# Power.net
KiCad netlist of a schematic drawn in EAGLE
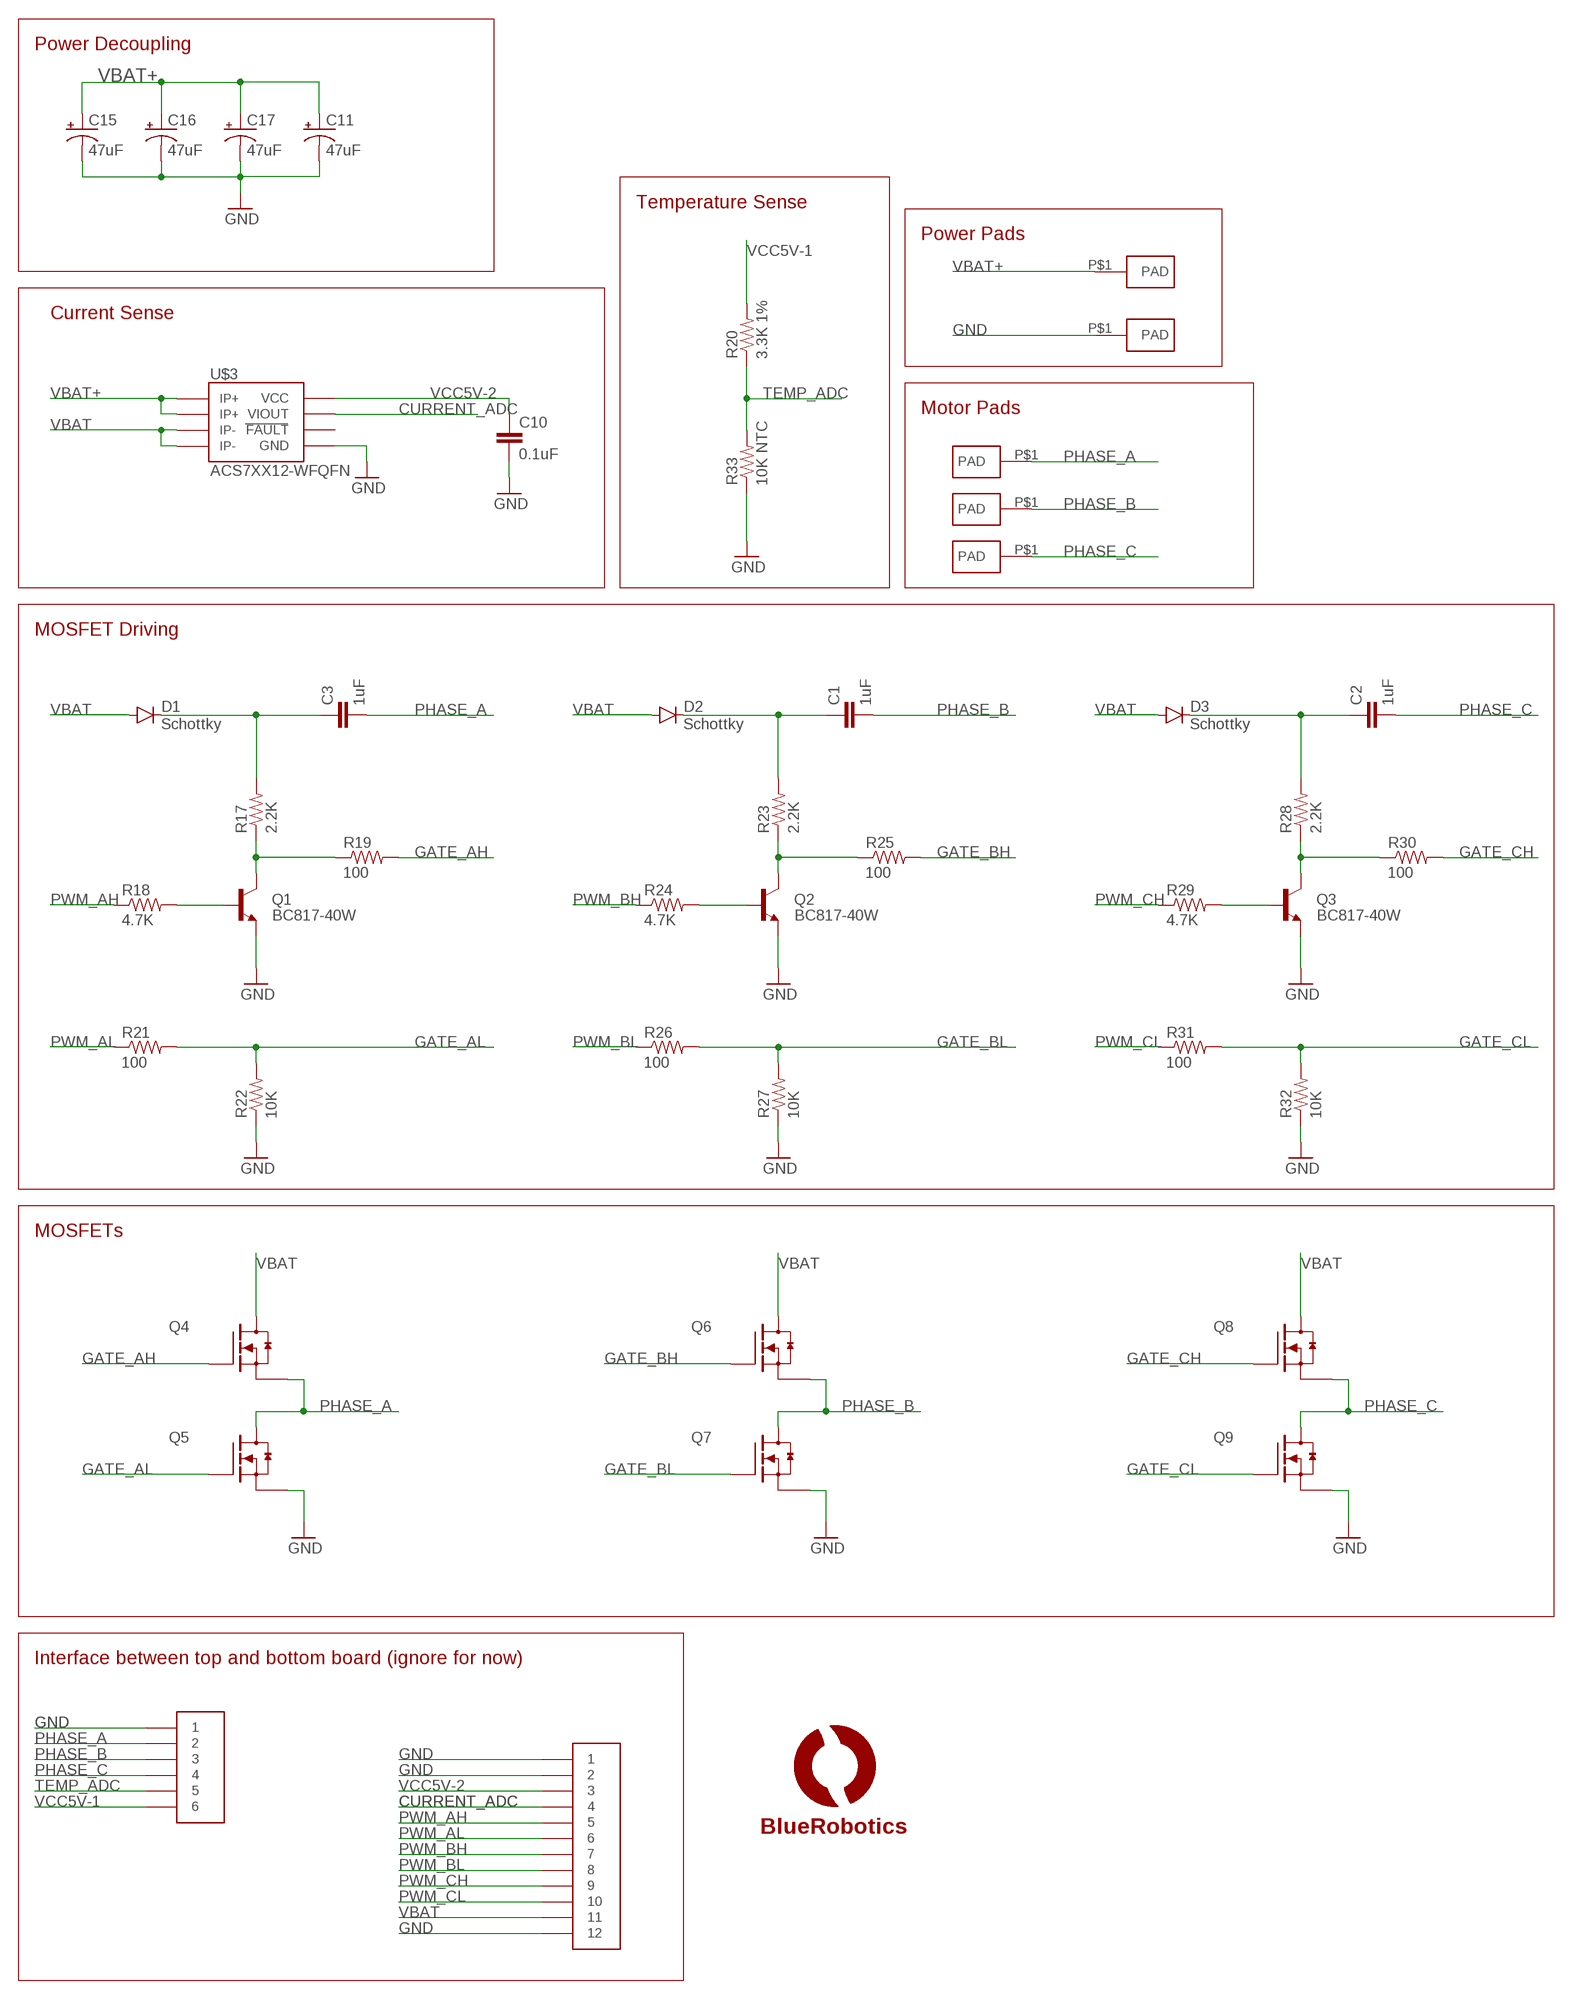
[diagram p0: schematic, sheet 1]

(export (version "E")
  (design (tool "Eeschema 10.0.6"))
  (components
    (comp (ref "C1")
      (value "1uF")
      (footprint "eagle-import:0805")
      (libsource (lib "eagle-import") (part "CAP0805"))
    )
    (comp (ref "C2")
      (value "1uF")
      (footprint "eagle-import:0805")
      (libsource (lib "eagle-import") (part "CAP0805"))
    )
    (comp (ref "C3")
      (value "1uF")
      (footprint "eagle-import:0805")
      (libsource (lib "eagle-import") (part "CAP0805"))
    )
    (comp (ref "C10")
      (value "0.1uF")
      (footprint "eagle-import:0603-CAP")
      (libsource (lib "eagle-import") (part "CAP0603-CAP"))
    )
    (comp (ref "C11")
      (value "47uF")
      (footprint "eagle-import:EIA7343")
      (libsource (lib "eagle-import") (part "CAP_POL7343"))
    )
    (comp (ref "C15")
      (value "47uF")
      (footprint "eagle-import:EIA7343")
      (libsource (lib "eagle-import") (part "CAP_POL7343"))
    )
    (comp (ref "C16")
      (value "47uF")
      (footprint "eagle-import:EIA7343")
      (libsource (lib "eagle-import") (part "CAP_POL7343"))
    )
    (comp (ref "C17")
      (value "47uF")
      (footprint "eagle-import:EIA7343")
      (libsource (lib "eagle-import") (part "CAP_POL7343"))
    )
    (comp (ref "D1")
      (value "Schottky")
      (footprint "eagle-import:SOD-323")
      (libsource (lib "eagle-import") (part "DIODESOD"))
    )
    (comp (ref "D2")
      (value "Schottky")
      (footprint "eagle-import:SOD-323")
      (libsource (lib "eagle-import") (part "DIODESOD"))
    )
    (comp (ref "D3")
      (value "Schottky")
      (footprint "eagle-import:SOD-323")
      (libsource (lib "eagle-import") (part "DIODESOD"))
    )
    (comp (ref "Q1")
      (value "BC817-40W")
      (footprint "eagle-import:SOT23")
      (libsource (lib "eagle-import") (part "TRANSISTOR_NPNSOT23"))
    )
    (comp (ref "Q2")
      (value "BC817-40W")
      (footprint "eagle-import:SOT23")
      (libsource (lib "eagle-import") (part "TRANSISTOR_NPNSOT23"))
    )
    (comp (ref "Q3")
      (value "BC817-40W")
      (footprint "eagle-import:SOT23")
      (libsource (lib "eagle-import") (part "TRANSISTOR_NPNSOT23"))
    )
    (comp (ref "Q4")
      (value "SI7370")
      (footprint "eagle-import:POWERPAK-SO-08")
      (libsource (lib "eagle-import") (part "SI7370"))
    )
    (comp (ref "Q5")
      (value "SI7370")
      (footprint "eagle-import:POWERPAK-SO-08")
      (libsource (lib "eagle-import") (part "SI7370"))
    )
    (comp (ref "Q6")
      (value "SI7370")
      (footprint "eagle-import:POWERPAK-SO-08")
      (libsource (lib "eagle-import") (part "SI7370"))
    )
    (comp (ref "Q7")
      (value "SI7370")
      (footprint "eagle-import:POWERPAK-SO-08")
      (libsource (lib "eagle-import") (part "SI7370"))
    )
    (comp (ref "Q8")
      (value "SI7370")
      (footprint "eagle-import:POWERPAK-SO-08")
      (libsource (lib "eagle-import") (part "SI7370"))
    )
    (comp (ref "Q9")
      (value "SI7370")
      (footprint "eagle-import:POWERPAK-SO-08")
      (libsource (lib "eagle-import") (part "SI7370"))
    )
    (comp (ref "R17")
      (value "2.2K")
      (footprint "eagle-import:0603-RES")
      (libsource (lib "eagle-import") (part "33KOHM1/10W1%(0603)"))
    )
    (comp (ref "R18")
      (value "4.7K")
      (footprint "eagle-import:0603-RES")
      (libsource (lib "eagle-import") (part "33KOHM1/10W1%(0603)"))
    )
    (comp (ref "R19")
      (value "100")
      (footprint "eagle-import:0603-RES")
      (libsource (lib "eagle-import") (part "33KOHM1/10W1%(0603)"))
    )
    (comp (ref "R20")
      (value "3.3K 1%")
      (footprint "eagle-import:0603-RES")
      (libsource (lib "eagle-import") (part "33KOHM1/10W1%(0603)"))
    )
    (comp (ref "R21")
      (value "100")
      (footprint "eagle-import:0603-RES")
      (libsource (lib "eagle-import") (part "33KOHM1/10W1%(0603)"))
    )
    (comp (ref "R22")
      (value "10K")
      (footprint "eagle-import:0603-RES")
      (libsource (lib "eagle-import") (part "33KOHM1/10W1%(0603)"))
    )
    (comp (ref "R23")
      (value "2.2K")
      (footprint "eagle-import:0603-RES")
      (libsource (lib "eagle-import") (part "33KOHM1/10W1%(0603)"))
    )
    (comp (ref "R24")
      (value "4.7K")
      (footprint "eagle-import:0603-RES")
      (libsource (lib "eagle-import") (part "33KOHM1/10W1%(0603)"))
    )
    (comp (ref "R25")
      (value "100")
      (footprint "eagle-import:0603-RES")
      (libsource (lib "eagle-import") (part "33KOHM1/10W1%(0603)"))
    )
    (comp (ref "R26")
      (value "100")
      (footprint "eagle-import:0603-RES")
      (libsource (lib "eagle-import") (part "33KOHM1/10W1%(0603)"))
    )
    (comp (ref "R27")
      (value "10K")
      (footprint "eagle-import:0603-RES")
      (libsource (lib "eagle-import") (part "33KOHM1/10W1%(0603)"))
    )
    (comp (ref "R28")
      (value "2.2K")
      (footprint "eagle-import:0603-RES")
      (libsource (lib "eagle-import") (part "33KOHM1/10W1%(0603)"))
    )
    (comp (ref "R29")
      (value "4.7K")
      (footprint "eagle-import:0603-RES")
      (libsource (lib "eagle-import") (part "33KOHM1/10W1%(0603)"))
    )
    (comp (ref "R30")
      (value "100")
      (footprint "eagle-import:0603-RES")
      (libsource (lib "eagle-import") (part "33KOHM1/10W1%(0603)"))
    )
    (comp (ref "R31")
      (value "100")
      (footprint "eagle-import:0603-RES")
      (libsource (lib "eagle-import") (part "33KOHM1/10W1%(0603)"))
    )
    (comp (ref "R32")
      (value "10K")
      (footprint "eagle-import:0603-RES")
      (libsource (lib "eagle-import") (part "33KOHM1/10W1%(0603)"))
    )
    (comp (ref "R33")
      (value "10K NTC")
      (footprint "eagle-import:0603-RES")
      (libsource (lib "eagle-import") (part "33KOHM1/10W1%(0603)"))
    )
    (comp (ref "U$1")
      (value "PADPTH-MED")
      (footprint "eagle-import:PAD-PTH-MED-1")
      (libsource (lib "eagle-import") (part "PADPTH-MED"))
    )
    (comp (ref "U$2")
      (value "PADPTH-MED")
      (footprint "eagle-import:PAD-PTH-MED-1")
      (libsource (lib "eagle-import") (part "PADPTH-MED"))
    )
    (comp (ref "U$3")
      (value "ACS7XX12-WFQFN")
      (footprint "eagle-import:12-WFQFN")
      (libsource (lib "eagle-import") (part "ACS7XX12-WFQFN"))
    )
    (comp (ref "U$4")
      (value "HEADER-62MM")
      (footprint "eagle-import:HEADER-2MM-6POS")
      (libsource (lib "eagle-import") (part "HEADER-62MM"))
    )
    (comp (ref "U$5")
      (value "PAD2X3MM")
      (footprint "eagle-import:PAD-2X3MM")
      (libsource (lib "eagle-import") (part "PAD2X3MM"))
    )
    (comp (ref "U$6")
      (value "PAD2X3MM")
      (footprint "eagle-import:PAD-2X3MM")
      (libsource (lib "eagle-import") (part "PAD2X3MM"))
    )
    (comp (ref "U$7")
      (value "PAD2X3MM")
      (footprint "eagle-import:PAD-2X3MM")
      (libsource (lib "eagle-import") (part "PAD2X3MM"))
    )
    (comp (ref "U$8")
      (value "HEADER-122MM")
      (footprint "eagle-import:HEADER-2MM-12POS")
      (libsource (lib "eagle-import") (part "HEADER-122MM"))
    )
    (comp (ref "U$9")
      (value "LOGOBR-LOGO-S")
      (footprint "eagle-import:BR-LOGO-SMALL")
      (libsource (lib "eagle-import") (part "LOGOBR-LOGO-S"))
    )
  )
  (nets
    (net (code "1") (name "/CURRENT_ADC") (class "Default")
      (node (ref "U$3") (pin "VIOUT") (pinfunction "VIOUT_VIOUT") (pintype "bidirectional"))
      (node (ref "U$8") (pin "P$4") (pinfunction "4_P$4") (pintype "bidirectional"))
    )
    (net (code "2") (name "/GATE_AH") (class "Default")
      (node (ref "Q4") (pin "4") (pinfunction "G_4") (pintype "passive"))
      (node (ref "R19") (pin "2") (pinfunction "2_2") (pintype "passive"))
    )
    (net (code "3") (name "/GATE_AL") (class "Default")
      (node (ref "Q5") (pin "4") (pinfunction "G_4") (pintype "passive"))
      (node (ref "R21") (pin "2") (pinfunction "2_2") (pintype "passive"))
      (node (ref "R22") (pin "2") (pinfunction "2_2") (pintype "passive"))
    )
    (net (code "4") (name "/GATE_BH") (class "Default")
      (node (ref "Q6") (pin "4") (pinfunction "G_4") (pintype "passive"))
      (node (ref "R25") (pin "2") (pinfunction "2_2") (pintype "passive"))
    )
    (net (code "5") (name "/GATE_BL") (class "Default")
      (node (ref "Q7") (pin "4") (pinfunction "G_4") (pintype "passive"))
      (node (ref "R26") (pin "2") (pinfunction "2_2") (pintype "passive"))
      (node (ref "R27") (pin "2") (pinfunction "2_2") (pintype "passive"))
    )
    (net (code "6") (name "/GATE_CH") (class "Default")
      (node (ref "Q8") (pin "4") (pinfunction "G_4") (pintype "passive"))
      (node (ref "R30") (pin "2") (pinfunction "2_2") (pintype "passive"))
    )
    (net (code "7") (name "/GATE_CL") (class "Default")
      (node (ref "Q9") (pin "4") (pinfunction "G_4") (pintype "passive"))
      (node (ref "R31") (pin "2") (pinfunction "2_2") (pintype "passive"))
      (node (ref "R32") (pin "2") (pinfunction "2_2") (pintype "passive"))
    )
    (net (code "8") (name "/PHASE_A") (class "Default")
      (node (ref "C3") (pin "2") (pinfunction "2_2") (pintype "passive"))
      (node (ref "Q4") (pin "3") (pinfunction "S3_3") (pintype "passive"))
      (node (ref "Q5") (pin "5-8") (pinfunction "D_5-8") (pintype "passive"))
      (node (ref "U$4") (pin "P$2") (pinfunction "2_P$2") (pintype "bidirectional"))
      (node (ref "U$5") (pin "P$1") (pinfunction "PAD_P$1") (pintype "bidirectional"))
    )
    (net (code "9") (name "/PHASE_B") (class "Default")
      (node (ref "C1") (pin "2") (pinfunction "2_2") (pintype "passive"))
      (node (ref "Q6") (pin "3") (pinfunction "S3_3") (pintype "passive"))
      (node (ref "Q7") (pin "5-8") (pinfunction "D_5-8") (pintype "passive"))
      (node (ref "U$4") (pin "P$3") (pinfunction "3_P$3") (pintype "bidirectional"))
      (node (ref "U$6") (pin "P$1") (pinfunction "PAD_P$1") (pintype "bidirectional"))
    )
    (net (code "10") (name "/PHASE_C") (class "Default")
      (node (ref "C2") (pin "2") (pinfunction "2_2") (pintype "passive"))
      (node (ref "Q8") (pin "3") (pinfunction "S3_3") (pintype "passive"))
      (node (ref "Q9") (pin "5-8") (pinfunction "D_5-8") (pintype "passive"))
      (node (ref "U$4") (pin "P$4") (pinfunction "4_P$4") (pintype "bidirectional"))
      (node (ref "U$7") (pin "P$1") (pinfunction "PAD_P$1") (pintype "bidirectional"))
    )
    (net (code "11") (name "/PWM_AH") (class "Default")
      (node (ref "R18") (pin "1") (pinfunction "1_1") (pintype "passive"))
      (node (ref "U$8") (pin "P$5") (pinfunction "5_P$5") (pintype "bidirectional"))
    )
    (net (code "12") (name "/PWM_AL") (class "Default")
      (node (ref "R21") (pin "1") (pinfunction "1_1") (pintype "passive"))
      (node (ref "U$8") (pin "P$6") (pinfunction "6_P$6") (pintype "bidirectional"))
    )
    (net (code "13") (name "/PWM_BH") (class "Default")
      (node (ref "R24") (pin "1") (pinfunction "1_1") (pintype "passive"))
      (node (ref "U$8") (pin "P$7") (pinfunction "7_P$7") (pintype "bidirectional"))
    )
    (net (code "14") (name "/PWM_BL") (class "Default")
      (node (ref "R26") (pin "1") (pinfunction "1_1") (pintype "passive"))
      (node (ref "U$8") (pin "P$8") (pinfunction "8_P$8") (pintype "bidirectional"))
    )
    (net (code "15") (name "/PWM_CH") (class "Default")
      (node (ref "R29") (pin "1") (pinfunction "1_1") (pintype "passive"))
      (node (ref "U$8") (pin "P$9") (pinfunction "9_P$9") (pintype "bidirectional"))
    )
    (net (code "16") (name "/PWM_CL") (class "Default")
      (node (ref "R31") (pin "1") (pinfunction "1_1") (pintype "passive"))
      (node (ref "U$8") (pin "P$10") (pinfunction "10_P$10") (pintype "bidirectional"))
    )
    (net (code "17") (name "/TEMP_ADC") (class "Default")
      (node (ref "R20") (pin "1") (pinfunction "1_1") (pintype "passive"))
      (node (ref "R33") (pin "2") (pinfunction "2_2") (pintype "passive"))
      (node (ref "U$4") (pin "P$5") (pinfunction "5_P$5") (pintype "bidirectional"))
    )
    (net (code "18") (name "/VBAT") (class "Default")
      (node (ref "D1") (pin "A") (pinfunction "A_A") (pintype "passive"))
      (node (ref "D2") (pin "A") (pinfunction "A_A") (pintype "passive"))
      (node (ref "D3") (pin "A") (pinfunction "A_A") (pintype "passive"))
      (node (ref "Q4") (pin "5-8") (pinfunction "D_5-8") (pintype "passive"))
      (node (ref "Q6") (pin "5-8") (pinfunction "D_5-8") (pintype "passive"))
      (node (ref "Q8") (pin "5-8") (pinfunction "D_5-8") (pintype "passive"))
      (node (ref "U$3") (pin "IP-1") (pinfunction "IP-1_IP-1") (pintype "bidirectional"))
      (node (ref "U$3") (pin "IP-2") (pinfunction "IP-2_IP-2") (pintype "bidirectional"))
      (node (ref "U$8") (pin "P$11") (pinfunction "11_P$11") (pintype "bidirectional"))
    )
    (net (code "19") (name "/VBAT+") (class "Default")
      (node (ref "C11") (pin "A") (pinfunction "+_A") (pintype "passive"))
      (node (ref "C15") (pin "A") (pinfunction "+_A") (pintype "passive"))
      (node (ref "C16") (pin "A") (pinfunction "+_A") (pintype "passive"))
      (node (ref "C17") (pin "A") (pinfunction "+_A") (pintype "passive"))
      (node (ref "U$1") (pin "P$1") (pinfunction "PAD_P$1") (pintype "bidirectional"))
      (node (ref "U$3") (pin "IP+1") (pinfunction "IP+1_IP+1") (pintype "bidirectional"))
      (node (ref "U$3") (pin "IP+2") (pinfunction "IP+2_IP+2") (pintype "bidirectional"))
    )
    (net (code "20") (name "/VCC5V-1") (class "Default")
      (node (ref "R20") (pin "2") (pinfunction "2_2") (pintype "passive"))
      (node (ref "U$4") (pin "P$6") (pinfunction "6_P$6") (pintype "bidirectional"))
    )
    (net (code "21") (name "/VCC5V-2") (class "Default")
      (node (ref "C10") (pin "1") (pinfunction "1_1") (pintype "passive"))
      (node (ref "U$3") (pin "VCC") (pinfunction "VCC_VCC") (pintype "power_in"))
      (node (ref "U$8") (pin "P$3") (pinfunction "3_P$3") (pintype "bidirectional"))
    )
    (net (code "22") (name "GND") (class "Default")
      (node (ref "C10") (pin "2") (pinfunction "2_2") (pintype "passive"))
      (node (ref "C11") (pin "C") (pinfunction "-_C") (pintype "passive"))
      (node (ref "C15") (pin "C") (pinfunction "-_C") (pintype "passive"))
      (node (ref "C16") (pin "C") (pinfunction "-_C") (pintype "passive"))
      (node (ref "C17") (pin "C") (pinfunction "-_C") (pintype "passive"))
      (node (ref "Q1") (pin "2") (pinfunction "E_2") (pintype "passive"))
      (node (ref "Q2") (pin "2") (pinfunction "E_2") (pintype "passive"))
      (node (ref "Q3") (pin "2") (pinfunction "E_2") (pintype "passive"))
      (node (ref "Q5") (pin "3") (pinfunction "S3_3") (pintype "passive"))
      (node (ref "Q7") (pin "3") (pinfunction "S3_3") (pintype "passive"))
      (node (ref "Q9") (pin "3") (pinfunction "S3_3") (pintype "passive"))
      (node (ref "R22") (pin "1") (pinfunction "1_1") (pintype "passive"))
      (node (ref "R27") (pin "1") (pinfunction "1_1") (pintype "passive"))
      (node (ref "R32") (pin "1") (pinfunction "1_1") (pintype "passive"))
      (node (ref "R33") (pin "1") (pinfunction "1_1") (pintype "passive"))
      (node (ref "U$2") (pin "P$1") (pinfunction "PAD_P$1") (pintype "bidirectional"))
      (node (ref "U$3") (pin "GND") (pinfunction "GND_GND") (pintype "power_in"))
      (node (ref "U$4") (pin "P$1") (pinfunction "1_P$1") (pintype "bidirectional"))
      (node (ref "U$8") (pin "P$1") (pinfunction "1_P$1") (pintype "bidirectional"))
      (node (ref "U$8") (pin "P$12") (pinfunction "12_P$12") (pintype "bidirectional"))
      (node (ref "U$8") (pin "P$2") (pinfunction "2_P$2") (pintype "bidirectional"))
    )
    (net (code "23") (name "Net-(C1-Pad1)") (class "Default")
      (node (ref "C1") (pin "1") (pinfunction "1_1") (pintype "passive"))
      (node (ref "D2") (pin "C") (pinfunction "C_C") (pintype "passive"))
      (node (ref "R23") (pin "2") (pinfunction "2_2") (pintype "passive"))
    )
    (net (code "24") (name "Net-(C2-Pad1)") (class "Default")
      (node (ref "C2") (pin "1") (pinfunction "1_1") (pintype "passive"))
      (node (ref "D3") (pin "C") (pinfunction "C_C") (pintype "passive"))
      (node (ref "R28") (pin "2") (pinfunction "2_2") (pintype "passive"))
    )
    (net (code "25") (name "Net-(C3-Pad1)") (class "Default")
      (node (ref "C3") (pin "1") (pinfunction "1_1") (pintype "passive"))
      (node (ref "D1") (pin "C") (pinfunction "C_C") (pintype "passive"))
      (node (ref "R17") (pin "2") (pinfunction "2_2") (pintype "passive"))
    )
    (net (code "26") (name "Net-(Q1-B)") (class "Default")
      (node (ref "Q1") (pin "1") (pinfunction "B_1") (pintype "passive"))
      (node (ref "R18") (pin "2") (pinfunction "2_2") (pintype "passive"))
    )
    (net (code "27") (name "Net-(Q1-C)") (class "Default")
      (node (ref "Q1") (pin "3") (pinfunction "C_3") (pintype "passive"))
      (node (ref "R17") (pin "1") (pinfunction "1_1") (pintype "passive"))
      (node (ref "R19") (pin "1") (pinfunction "1_1") (pintype "passive"))
    )
    (net (code "28") (name "Net-(Q2-B)") (class "Default")
      (node (ref "Q2") (pin "1") (pinfunction "B_1") (pintype "passive"))
      (node (ref "R24") (pin "2") (pinfunction "2_2") (pintype "passive"))
    )
    (net (code "29") (name "Net-(Q2-C)") (class "Default")
      (node (ref "Q2") (pin "3") (pinfunction "C_3") (pintype "passive"))
      (node (ref "R23") (pin "1") (pinfunction "1_1") (pintype "passive"))
      (node (ref "R25") (pin "1") (pinfunction "1_1") (pintype "passive"))
    )
    (net (code "30") (name "Net-(Q3-B)") (class "Default")
      (node (ref "Q3") (pin "1") (pinfunction "B_1") (pintype "passive"))
      (node (ref "R29") (pin "2") (pinfunction "2_2") (pintype "passive"))
    )
    (net (code "31") (name "Net-(Q3-C)") (class "Default")
      (node (ref "Q3") (pin "3") (pinfunction "C_3") (pintype "passive"))
      (node (ref "R28") (pin "1") (pinfunction "1_1") (pintype "passive"))
      (node (ref "R30") (pin "1") (pinfunction "1_1") (pintype "passive"))
    )
    (net (code "32") (name "unconnected-(Q4-S1-Pad1)") (class "Default")
      (node (ref "Q4") (pin "1") (pinfunction "S1_1") (pintype "passive"))
    )
    (net (code "33") (name "unconnected-(Q4-S2-Pad2)") (class "Default")
      (node (ref "Q4") (pin "2") (pinfunction "S2_2") (pintype "passive"))
    )
    (net (code "34") (name "unconnected-(Q5-S1-Pad1)") (class "Default")
      (node (ref "Q5") (pin "1") (pinfunction "S1_1") (pintype "passive"))
    )
    (net (code "35") (name "unconnected-(Q5-S2-Pad2)") (class "Default")
      (node (ref "Q5") (pin "2") (pinfunction "S2_2") (pintype "passive"))
    )
    (net (code "36") (name "unconnected-(Q6-S1-Pad1)") (class "Default")
      (node (ref "Q6") (pin "1") (pinfunction "S1_1") (pintype "passive"))
    )
    (net (code "37") (name "unconnected-(Q6-S2-Pad2)") (class "Default")
      (node (ref "Q6") (pin "2") (pinfunction "S2_2") (pintype "passive"))
    )
    (net (code "38") (name "unconnected-(Q7-S1-Pad1)") (class "Default")
      (node (ref "Q7") (pin "1") (pinfunction "S1_1") (pintype "passive"))
    )
    (net (code "39") (name "unconnected-(Q7-S2-Pad2)") (class "Default")
      (node (ref "Q7") (pin "2") (pinfunction "S2_2") (pintype "passive"))
    )
    (net (code "40") (name "unconnected-(Q8-S1-Pad1)") (class "Default")
      (node (ref "Q8") (pin "1") (pinfunction "S1_1") (pintype "passive"))
    )
    (net (code "41") (name "unconnected-(Q8-S2-Pad2)") (class "Default")
      (node (ref "Q8") (pin "2") (pinfunction "S2_2") (pintype "passive"))
    )
    (net (code "42") (name "unconnected-(Q9-S1-Pad1)") (class "Default")
      (node (ref "Q9") (pin "1") (pinfunction "S1_1") (pintype "passive"))
    )
    (net (code "43") (name "unconnected-(Q9-S2-Pad2)") (class "Default")
      (node (ref "Q9") (pin "2") (pinfunction "S2_2") (pintype "passive"))
    )
    (net (code "44") (name "unconnected-(U$3-PadFAULT)") (class "Default")
      (node (ref "U$3") (pin "FAULT") (pinfunction "FAULT_FAULT") (pintype "bidirectional"))
    )
  )
)
